# Power_Supply_Circuit.net
KiCad netlist of a schematic drawn in EAGLE
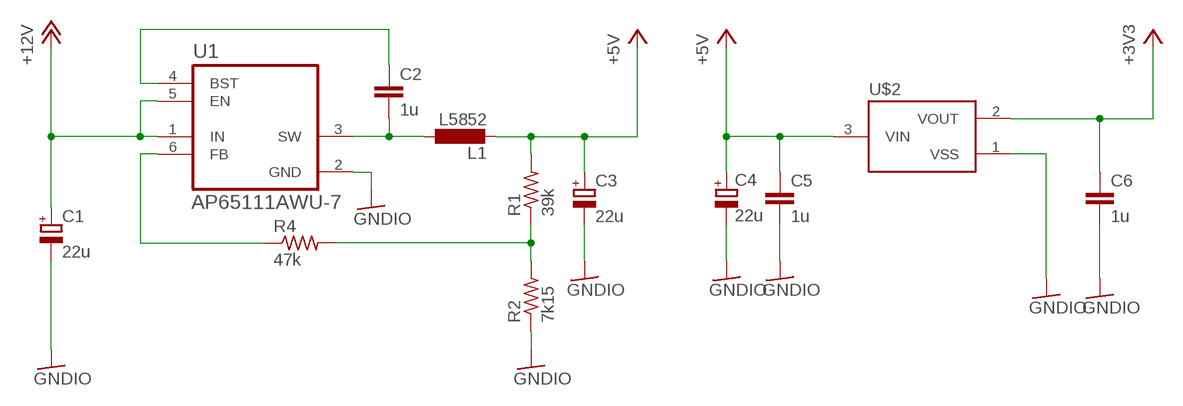
[diagram p0: schematic, sheet 1]

(export (version "E")
  (design (tool "Eeschema 10.0.6"))
  (components
    (comp (ref "C1")
      (value "22u")
      (footprint "eagle-import:E2-5")
      (libsource (lib "eagle-import") (part "CPOL-EUE2-5"))
    )
    (comp (ref "C2")
      (value "1u")
      (footprint "eagle-import:C0603")
      (libsource (lib "eagle-import") (part "C-EUC0603"))
    )
    (comp (ref "C3")
      (value "22u")
      (footprint "eagle-import:E2-5")
      (libsource (lib "eagle-import") (part "CPOL-EUE2-5"))
    )
    (comp (ref "C4")
      (value "22u")
      (footprint "eagle-import:E3,5-8")
      (libsource (lib "eagle-import") (part "CPOL-EUE3.5-8"))
    )
    (comp (ref "C5")
      (value "1u")
      (footprint "eagle-import:C0603")
      (libsource (lib "eagle-import") (part "C-EUC0603"))
    )
    (comp (ref "C6")
      (value "1u")
      (footprint "eagle-import:C0603")
      (libsource (lib "eagle-import") (part "C-EUC0603"))
    )
    (comp (ref "L1")
      (value "L5852")
      (footprint "eagle-import:L5852")
      (libsource (lib "eagle-import") (part "L5852"))
    )
    (comp (ref "R1")
      (value "39k")
      (footprint "eagle-import:R0603")
      (libsource (lib "eagle-import") (part "R-US_R0603"))
    )
    (comp (ref "R2")
      (value "7k15")
      (footprint "eagle-import:R0603")
      (libsource (lib "eagle-import") (part "R-US_R0603"))
    )
    (comp (ref "R4")
      (value "47k")
      (footprint "eagle-import:R0603")
      (libsource (lib "eagle-import") (part "R-US_R0603"))
    )
    (comp (ref "U$2")
      (value "AP2120")
      (footprint "eagle-import:SOT95P240X110-3")
      (libsource (lib "eagle-import") (part "AP2120"))
    )
    (comp (ref "U1")
      (value "AP65111AWU-7")
      (footprint "eagle-import:SOT95P280X100-6N")
      (fields (field (name "DIGI-KEY_PART_NUMBER") "AP65111AWU-7DICT-ND") (field (name "MF") "Diodes Inc."))
      (libsource (lib "eagle-import") (part "AP65111AWU-7"))
    )
  )
  (nets
    (net (code "1") (name "+3V3") (class "Default")
      (node (ref "C6") (pin "1") (pinfunction "1_1") (pintype "passive"))
      (node (ref "U$2") (pin "2") (pinfunction "VOUT_2") (pintype "bidirectional"))
    )
    (net (code "2") (name "+5V") (class "Default")
      (node (ref "C3") (pin "+") (pinfunction "+_+") (pintype "passive"))
      (node (ref "C4") (pin "+") (pinfunction "+_+") (pintype "passive"))
      (node (ref "C5") (pin "1") (pinfunction "1_1") (pintype "passive"))
      (node (ref "L1") (pin "P$2") (pinfunction "2_P$2") (pintype "passive"))
      (node (ref "R1") (pin "2") (pinfunction "2_2") (pintype "passive"))
      (node (ref "U$2") (pin "3") (pinfunction "VIN_3") (pintype "bidirectional"))
    )
    (net (code "3") (name "+12V") (class "Default")
      (node (ref "C1") (pin "+") (pinfunction "+_+") (pintype "passive"))
      (node (ref "U1") (pin "1") (pinfunction "IN_1") (pintype "input"))
      (node (ref "U1") (pin "5") (pinfunction "EN_5") (pintype "input"))
    )
    (net (code "4") (name "GNDIO") (class "Default")
      (node (ref "C1") (pin "-") (pinfunction "-_-") (pintype "passive"))
      (node (ref "C3") (pin "-") (pinfunction "-_-") (pintype "passive"))
      (node (ref "C4") (pin "-") (pinfunction "-_-") (pintype "passive"))
      (node (ref "C5") (pin "2") (pinfunction "2_2") (pintype "passive"))
      (node (ref "C6") (pin "2") (pinfunction "2_2") (pintype "passive"))
      (node (ref "R2") (pin "1") (pinfunction "1_1") (pintype "passive"))
      (node (ref "U$2") (pin "1") (pinfunction "VSS_1") (pintype "bidirectional"))
      (node (ref "U1") (pin "2") (pinfunction "GND_2") (pintype "power_in"))
    )
    (net (code "5") (name "Net-(L1-1)") (class "Default")
      (node (ref "C2") (pin "2") (pinfunction "2_2") (pintype "passive"))
      (node (ref "L1") (pin "P$1") (pinfunction "1_P$1") (pintype "passive"))
      (node (ref "U1") (pin "3") (pinfunction "SW_3") (pintype "output"))
    )
    (net (code "6") (name "Net-(R1-Pad1)") (class "Default")
      (node (ref "R1") (pin "1") (pinfunction "1_1") (pintype "passive"))
      (node (ref "R2") (pin "2") (pinfunction "2_2") (pintype "passive"))
      (node (ref "R4") (pin "2") (pinfunction "2_2") (pintype "passive"))
    )
    (net (code "7") (name "Net-(U1-BST)") (class "Default")
      (node (ref "C2") (pin "1") (pinfunction "1_1") (pintype "passive"))
      (node (ref "U1") (pin "4") (pinfunction "BST_4") (pintype "input"))
    )
    (net (code "8") (name "Net-(U1-FB)") (class "Default")
      (node (ref "R4") (pin "1") (pinfunction "1_1") (pintype "passive"))
      (node (ref "U1") (pin "6") (pinfunction "FB_6") (pintype "input"))
    )
  )
)
